# power.net
KiCad netlist of a schematic drawn in Altium Designer
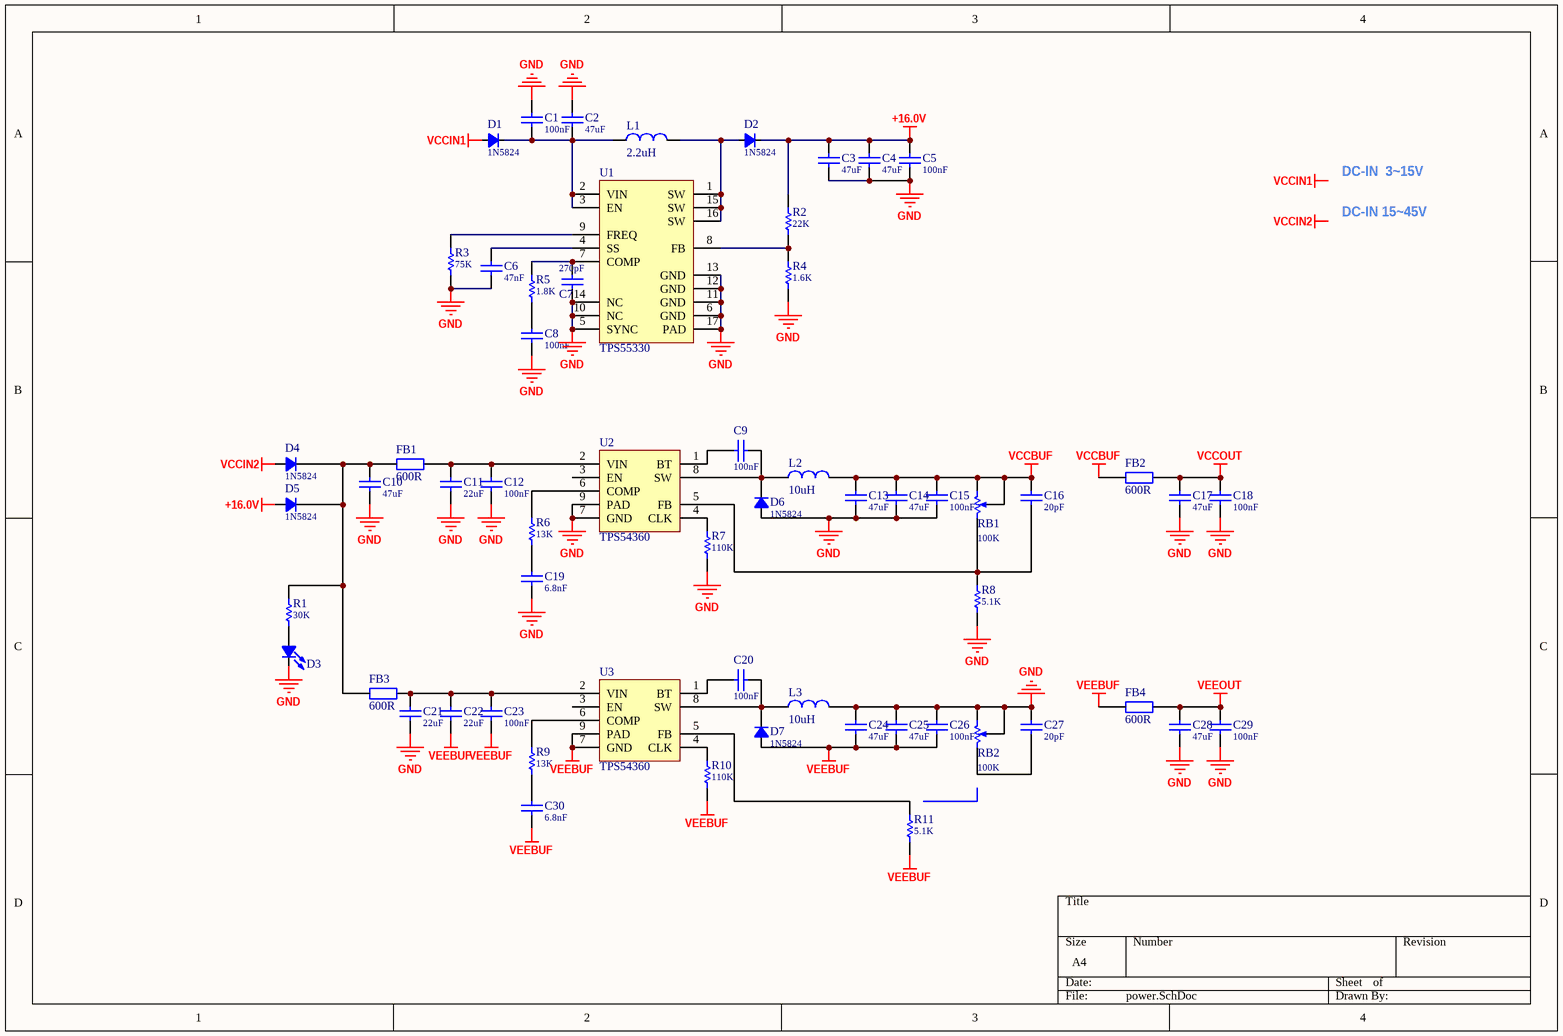
[diagram p0: power.SchDoc]

(export (version "E")
  (design (tool "Eeschema 10.0.6"))
  (components
    (comp (ref "C1")
      (value "100nF")
      (footprint "C0603-L")
      (description "贴片瓷片电容")
      (fields (field (name "Comment") "Cap-S"))
      (libsource (lib "xz_D") (part "Cap-S"))
    )
    (comp (ref "C2")
      (value "47uF")
      (footprint "C1206-L")
      (description "贴片瓷片电容")
      (fields (field (name "Comment") "Cap-S"))
      (libsource (lib "xz_D") (part "Cap-S"))
    )
    (comp (ref "C3")
      (value "47uF")
      (footprint "C1206-L")
      (description "贴片瓷片电容")
      (fields (field (name "Comment") "Cap-S"))
      (libsource (lib "xz_D") (part "Cap-S"))
    )
    (comp (ref "C4")
      (value "47uF")
      (footprint "C1206-L")
      (description "贴片瓷片电容")
      (fields (field (name "Comment") "Cap-S"))
      (libsource (lib "xz_D") (part "Cap-S"))
    )
    (comp (ref "C5")
      (value "100nF")
      (footprint "C0603-L")
      (description "贴片瓷片电容")
      (fields (field (name "Comment") "Cap-S"))
      (libsource (lib "xz_D") (part "Cap-S"))
    )
    (comp (ref "C6")
      (value "47nF")
      (footprint "C0603-L")
      (description "贴片瓷片电容")
      (fields (field (name "Comment") "Cap-S"))
      (libsource (lib "xz_D") (part "Cap-S"))
    )
    (comp (ref "C7")
      (value "270pF")
      (footprint "C0603-L")
      (description "贴片瓷片电容")
      (fields (field (name "Comment") "Cap-S"))
      (libsource (lib "xz_D") (part "Cap-S"))
    )
    (comp (ref "C8")
      (value "100nF")
      (footprint "C0603-L")
      (description "贴片瓷片电容")
      (fields (field (name "Comment") "Cap-S"))
      (libsource (lib "xz_D") (part "Cap-S"))
    )
    (comp (ref "C9")
      (value "100nF")
      (footprint "C0603-L")
      (description "贴片瓷片电容")
      (fields (field (name "Comment") "Cap-S"))
      (libsource (lib "xz_D") (part "Cap-S"))
    )
    (comp (ref "C10")
      (value "47uF")
      (footprint "C1206-L")
      (description "贴片瓷片电容")
      (fields (field (name "Comment") "Cap-S"))
      (libsource (lib "xz_D") (part "Cap-S"))
    )
    (comp (ref "C11")
      (value "22uF")
      (footprint "C1206-L")
      (description "贴片瓷片电容")
      (fields (field (name "Comment") "Cap-S"))
      (libsource (lib "xz_D") (part "Cap-S"))
    )
    (comp (ref "C12")
      (value "100nF")
      (footprint "C0603-L")
      (description "贴片瓷片电容")
      (fields (field (name "Comment") "Cap-S"))
      (libsource (lib "xz_D") (part "Cap-S"))
    )
    (comp (ref "C13")
      (value "47uF")
      (footprint "C1206-L")
      (description "贴片瓷片电容")
      (fields (field (name "Comment") "Cap-S"))
      (libsource (lib "xz_D") (part "Cap-S"))
    )
    (comp (ref "C14")
      (value "47uF")
      (footprint "C1206-L")
      (description "贴片瓷片电容")
      (fields (field (name "Comment") "Cap-S"))
      (libsource (lib "xz_D") (part "Cap-S"))
    )
    (comp (ref "C15")
      (value "100nF")
      (footprint "C0603-L")
      (description "贴片瓷片电容")
      (fields (field (name "Comment") "Cap-S"))
      (libsource (lib "xz_D") (part "Cap-S"))
    )
    (comp (ref "C16")
      (value "20pF")
      (footprint "C0603-L")
      (description "贴片瓷片电容")
      (fields (field (name "Comment") "Cap-S"))
      (libsource (lib "xz_D") (part "Cap-S"))
    )
    (comp (ref "C17")
      (value "47uF")
      (footprint "C1206-L")
      (description "贴片瓷片电容")
      (fields (field (name "Comment") "Cap-S"))
      (libsource (lib "xz_D") (part "Cap-S"))
    )
    (comp (ref "C18")
      (value "100nF")
      (footprint "C0603-L")
      (description "贴片瓷片电容")
      (fields (field (name "Comment") "Cap-S"))
      (libsource (lib "xz_D") (part "Cap-S"))
    )
    (comp (ref "C19")
      (value "6.8nF")
      (footprint "C0603-L")
      (description "贴片瓷片电容")
      (fields (field (name "Comment") "Cap-S"))
      (libsource (lib "xz_D") (part "Cap-S"))
    )
    (comp (ref "C20")
      (value "100nF")
      (footprint "C0603-L")
      (description "贴片瓷片电容")
      (fields (field (name "Comment") "Cap-S"))
      (libsource (lib "xz_D") (part "Cap-S"))
    )
    (comp (ref "C21")
      (value "22uF")
      (footprint "C1206-L")
      (description "贴片瓷片电容")
      (fields (field (name "Comment") "Cap-S"))
      (libsource (lib "xz_D") (part "Cap-S"))
    )
    (comp (ref "C22")
      (value "22uF")
      (footprint "C1206-L")
      (description "贴片瓷片电容")
      (fields (field (name "Comment") "Cap-S"))
      (libsource (lib "xz_D") (part "Cap-S"))
    )
    (comp (ref "C23")
      (value "100nF")
      (footprint "C0603-L")
      (description "贴片瓷片电容")
      (fields (field (name "Comment") "Cap-S"))
      (libsource (lib "xz_D") (part "Cap-S"))
    )
    (comp (ref "C24")
      (value "47uF")
      (footprint "C1206-L")
      (description "贴片瓷片电容")
      (fields (field (name "Comment") "Cap-S"))
      (libsource (lib "xz_D") (part "Cap-S"))
    )
    (comp (ref "C25")
      (value "47uF")
      (footprint "C1206-L")
      (description "贴片瓷片电容")
      (fields (field (name "Comment") "Cap-S"))
      (libsource (lib "xz_D") (part "Cap-S"))
    )
    (comp (ref "C26")
      (value "100nF")
      (footprint "C0603-L")
      (description "贴片瓷片电容")
      (fields (field (name "Comment") "Cap-S"))
      (libsource (lib "xz_D") (part "Cap-S"))
    )
    (comp (ref "C27")
      (value "20pF")
      (footprint "C0603-L")
      (description "贴片瓷片电容")
      (fields (field (name "Comment") "Cap-S"))
      (libsource (lib "xz_D") (part "Cap-S"))
    )
    (comp (ref "C28")
      (value "47uF")
      (footprint "C1206-L")
      (description "贴片瓷片电容")
      (fields (field (name "Comment") "Cap-S"))
      (libsource (lib "xz_D") (part "Cap-S"))
    )
    (comp (ref "C29")
      (value "100nF")
      (footprint "C0603-L")
      (description "贴片瓷片电容")
      (fields (field (name "Comment") "Cap-S"))
      (libsource (lib "xz_D") (part "Cap-S"))
    )
    (comp (ref "C30")
      (value "6.8nF")
      (footprint "C0603-L")
      (description "贴片瓷片电容")
      (fields (field (name "Comment") "Cap-S"))
      (libsource (lib "xz_D") (part "Cap-S"))
    )
    (comp (ref "D1")
      (value "D")
      (footprint "D-SMA")
      (description "二极管")
      (fields (field (name "MODEL") "1N5824"))
      (libsource (lib "xz_D") (part "Diode"))
    )
    (comp (ref "D2")
      (value "D")
      (footprint "D-SMA")
      (description "二极管")
      (fields (field (name "MODEL") "1N5824"))
      (libsource (lib "xz_D") (part "Diode"))
    )
    (comp (ref "D3")
      (value "LED")
      (footprint "Led-0805_M")
      (description "发光二极管")
      (libsource (lib "xz_D") (part "LED"))
    )
    (comp (ref "D4")
      (value "D")
      (footprint "D-SMA")
      (description "二极管")
      (fields (field (name "MODEL") "1N5824"))
      (libsource (lib "xz_D") (part "Diode"))
    )
    (comp (ref "D5")
      (value "D")
      (footprint "D-SMA")
      (description "二极管")
      (fields (field (name "MODEL") "1N5824"))
      (libsource (lib "xz_D") (part "Diode"))
    )
    (comp (ref "D6")
      (value "D")
      (footprint "D-SMA")
      (description "二极管")
      (fields (field (name "MODEL") "1N5824"))
      (libsource (lib "xz_D") (part "Diode"))
    )
    (comp (ref "D7")
      (value "D")
      (footprint "D-SMA")
      (description "二极管")
      (fields (field (name "MODEL") "1N5824"))
      (libsource (lib "xz_D") (part "Diode"))
    )
    (comp (ref "FB1") (value "600R") (footprint "FB-0805") (libsource (lib "CommonUsed") (part "FB")))
    (comp (ref "FB2") (value "600R") (footprint "FB-0805") (libsource (lib "CommonUsed") (part "FB")))
    (comp (ref "FB3") (value "600R") (footprint "FB-0805") (libsource (lib "CommonUsed") (part "FB")))
    (comp (ref "FB4") (value "600R") (footprint "FB-0805") (libsource (lib "CommonUsed") (part "FB")))
    (comp (ref "L1") (value "2.2uH") (footprint "L-6.5mm") (libsource (lib "CommonUsed") (part "Inductor")))
    (comp (ref "L2") (value "10uH") (footprint "L-6.5mm") (libsource (lib "CommonUsed") (part "Inductor")))
    (comp (ref "L3") (value "10uH") (footprint "L-6.5mm") (libsource (lib "CommonUsed") (part "Inductor")))
    (comp (ref "R1")
      (value "30K")
      (footprint "R0603-L")
      (description "贴片电阻")
      (fields (field (name "Comment") "R"))
      (libsource (lib "xz_D") (part "Res"))
    )
    (comp (ref "R2")
      (value "22K")
      (footprint "R0603-L")
      (description "贴片电阻")
      (fields (field (name "Comment") "R"))
      (libsource (lib "xz_D") (part "Res"))
    )
    (comp (ref "R3")
      (value "75K")
      (footprint "R0603-L")
      (description "贴片电阻")
      (fields (field (name "Comment") "R"))
      (libsource (lib "xz_D") (part "Res"))
    )
    (comp (ref "R4")
      (value "1.6K")
      (footprint "R0603-L")
      (description "贴片电阻")
      (fields (field (name "Comment") "R"))
      (libsource (lib "xz_D") (part "Res"))
    )
    (comp (ref "R5")
      (value "1.8K")
      (footprint "R0603-L")
      (description "贴片电阻")
      (fields (field (name "Comment") "R"))
      (libsource (lib "xz_D") (part "Res"))
    )
    (comp (ref "R6")
      (value "13K")
      (footprint "R0603-L")
      (description "贴片电阻")
      (fields (field (name "Comment") "R"))
      (libsource (lib "xz_D") (part "Res"))
    )
    (comp (ref "R7")
      (value "110K")
      (footprint "R0603-L")
      (description "贴片电阻")
      (fields (field (name "Comment") "R"))
      (libsource (lib "xz_D") (part "Res"))
    )
    (comp (ref "R8")
      (value "5.1K")
      (footprint "R0603-L")
      (description "贴片电阻")
      (fields (field (name "Comment") "R"))
      (libsource (lib "xz_D") (part "Res"))
    )
    (comp (ref "R9")
      (value "13K")
      (footprint "R0603-L")
      (description "贴片电阻")
      (fields (field (name "Comment") "R"))
      (libsource (lib "xz_D") (part "Res"))
    )
    (comp (ref "R10")
      (value "110K")
      (footprint "R0603-L")
      (description "贴片电阻")
      (fields (field (name "Comment") "R"))
      (libsource (lib "xz_D") (part "Res"))
    )
    (comp (ref "R11")
      (value "5.1K")
      (footprint "R0603-L")
      (description "贴片电阻")
      (fields (field (name "Comment") "R"))
      (libsource (lib "xz_D") (part "Res"))
    )
    (comp (ref "RB1")
      (value "100K")
      (footprint "R_VR-3296W")
      (description "可调电阻")
      (fields (field (name "Comment") "R"))
      (libsource (lib "xz_D") (part "Res_Val"))
    )
    (comp (ref "RB2")
      (value "100K")
      (footprint "R_VR-3296W")
      (description "可调电阻")
      (fields (field (name "Comment") "R"))
      (libsource (lib "xz_D") (part "Res_Val"))
    )
    (comp (ref "U1")
      (value "TPS55330")
      (footprint "VQFN-16")
      (libsource (lib "CommonUsed") (part "TPS55330"))
    )
    (comp (ref "U2")
      (value "TPS54360")
      (footprint "SOP-8 with pad")
      (libsource (lib "CommonUsed") (part "TPS54560"))
    )
    (comp (ref "U3")
      (value "TPS54360")
      (footprint "SOP-8 with pad")
      (libsource (lib "CommonUsed") (part "TPS54560"))
    )
  )
  (nets
    (net (code "1") (name "+16.0V") (class "Default")
      (node (ref "C3") (pin "2") (pinfunction "2_2") (pintype "passive"))
      (node (ref "C4") (pin "2") (pinfunction "2_2") (pintype "passive"))
      (node (ref "C5") (pin "2") (pinfunction "2_2") (pintype "passive"))
      (node (ref "D2") (pin "2") (pinfunction "K_2") (pintype "passive"))
      (node (ref "D5") (pin "1") (pinfunction "A_1") (pintype "passive"))
      (node (ref "R2") (pin "2") (pinfunction "2_2") (pintype "passive"))
    )
    (net (code "2") (name "GND") (class "Default")
      (node (ref "C1") (pin "2") (pinfunction "2_2") (pintype "passive"))
      (node (ref "C10") (pin "1") (pinfunction "1_1") (pintype "passive"))
      (node (ref "C11") (pin "1") (pinfunction "1_1") (pintype "passive"))
      (node (ref "C12") (pin "1") (pinfunction "1_1") (pintype "passive"))
      (node (ref "C13") (pin "1") (pinfunction "1_1") (pintype "passive"))
      (node (ref "C14") (pin "1") (pinfunction "1_1") (pintype "passive"))
      (node (ref "C15") (pin "1") (pinfunction "1_1") (pintype "passive"))
      (node (ref "C17") (pin "1") (pinfunction "1_1") (pintype "passive"))
      (node (ref "C18") (pin "1") (pinfunction "1_1") (pintype "passive"))
      (node (ref "C19") (pin "1") (pinfunction "1_1") (pintype "passive"))
      (node (ref "C2") (pin "2") (pinfunction "2_2") (pintype "passive"))
      (node (ref "C21") (pin "1") (pinfunction "1_1") (pintype "passive"))
      (node (ref "C24") (pin "2") (pinfunction "2_2") (pintype "passive"))
      (node (ref "C25") (pin "2") (pinfunction "2_2") (pintype "passive"))
      (node (ref "C26") (pin "2") (pinfunction "2_2") (pintype "passive"))
      (node (ref "C27") (pin "2") (pinfunction "2_2") (pintype "passive"))
      (node (ref "C28") (pin "1") (pinfunction "1_1") (pintype "passive"))
      (node (ref "C29") (pin "1") (pinfunction "1_1") (pintype "passive"))
      (node (ref "C3") (pin "1") (pinfunction "1_1") (pintype "passive"))
      (node (ref "C4") (pin "1") (pinfunction "1_1") (pintype "passive"))
      (node (ref "C5") (pin "1") (pinfunction "1_1") (pintype "passive"))
      (node (ref "C6") (pin "1") (pinfunction "1_1") (pintype "passive"))
      (node (ref "C7") (pin "1") (pinfunction "1_1") (pintype "passive"))
      (node (ref "C8") (pin "1") (pinfunction "1_1") (pintype "passive"))
      (node (ref "D3") (pin "2") (pinfunction "2_2") (pintype "passive"))
      (node (ref "D6") (pin "1") (pinfunction "A_1") (pintype "passive"))
      (node (ref "L3") (pin "2") (pinfunction "2_2") (pintype "passive"))
      (node (ref "R3") (pin "2") (pinfunction "2_2") (pintype "passive"))
      (node (ref "R4") (pin "1") (pinfunction "1_1") (pintype "passive"))
      (node (ref "R7") (pin "1") (pinfunction "1_1") (pintype "passive"))
      (node (ref "R8") (pin "1") (pinfunction "1_1") (pintype "passive"))
      (node (ref "RB2") (pin "2") (pinfunction "2_2") (pintype "passive"))
      (node (ref "RB2") (pin "3") (pinfunction "3_3") (pintype "passive"))
      (node (ref "U1") (pin "10") (pinfunction "NC_10") (pintype "passive"))
      (node (ref "U1") (pin "11") (pinfunction "GND_11") (pintype "passive"))
      (node (ref "U1") (pin "12") (pinfunction "GND_12") (pintype "passive"))
      (node (ref "U1") (pin "13") (pinfunction "GND_13") (pintype "passive"))
      (node (ref "U1") (pin "14") (pinfunction "NC_14") (pintype "passive"))
      (node (ref "U1") (pin "17") (pinfunction "PAD_17") (pintype "passive"))
      (node (ref "U1") (pin "5") (pinfunction "SYNC_5") (pintype "passive"))
      (node (ref "U1") (pin "6") (pinfunction "GND_6") (pintype "passive"))
      (node (ref "U2") (pin "7") (pinfunction "GND_7") (pintype "passive"))
      (node (ref "U2") (pin "9") (pinfunction "PAD_9") (pintype "passive"))
    )
    (net (code "3") (name "Net-(C8-Pad2)") (class "Default")
      (node (ref "C8") (pin "2") (pinfunction "2_2") (pintype "passive"))
      (node (ref "R5") (pin "2") (pinfunction "2_2") (pintype "passive"))
    )
    (net (code "4") (name "Net-(C19-Pad2)") (class "Default")
      (node (ref "C19") (pin "2") (pinfunction "2_2") (pintype "passive"))
      (node (ref "R6") (pin "1") (pinfunction "1_1") (pintype "passive"))
    )
    (net (code "5") (name "Net-(C27-Pad1)") (class "Default")
      (node (ref "C27") (pin "1") (pinfunction "1_1") (pintype "passive"))
      (node (ref "RB2") (pin "1") (pinfunction "1_1") (pintype "passive"))
    )
    (net (code "6") (name "Net-(C30-Pad2)") (class "Default")
      (node (ref "C30") (pin "2") (pinfunction "2_2") (pintype "passive"))
      (node (ref "R9") (pin "1") (pinfunction "1_1") (pintype "passive"))
    )
    (net (code "7") (name "Net-(D1-K)") (class "Default")
      (node (ref "C1") (pin "1") (pinfunction "1_1") (pintype "passive"))
      (node (ref "C2") (pin "1") (pinfunction "1_1") (pintype "passive"))
      (node (ref "D1") (pin "2") (pinfunction "K_2") (pintype "passive"))
      (node (ref "L1") (pin "1") (pinfunction "1_1") (pintype "passive"))
      (node (ref "U1") (pin "2") (pinfunction "VIN_2") (pintype "passive"))
      (node (ref "U1") (pin "3") (pinfunction "EN_3") (pintype "passive"))
    )
    (net (code "8") (name "Net-(D2-A)") (class "Default")
      (node (ref "D2") (pin "1") (pinfunction "A_1") (pintype "passive"))
      (node (ref "L1") (pin "2") (pinfunction "2_2") (pintype "passive"))
      (node (ref "U1") (pin "1") (pinfunction "SW_1") (pintype "passive"))
      (node (ref "U1") (pin "15") (pinfunction "SW_15") (pintype "passive"))
      (node (ref "U1") (pin "16") (pinfunction "SW_16") (pintype "passive"))
    )
    (net (code "9") (name "Net-(D3-Pad1)") (class "Default")
      (node (ref "D3") (pin "1") (pinfunction "1_1") (pintype "passive"))
      (node (ref "R1") (pin "1") (pinfunction "1_1") (pintype "passive"))
    )
    (net (code "10") (name "Net-(D4-K)") (class "Default")
      (node (ref "C10") (pin "2") (pinfunction "2_2") (pintype "passive"))
      (node (ref "D4") (pin "2") (pinfunction "K_2") (pintype "passive"))
      (node (ref "D5") (pin "2") (pinfunction "K_2") (pintype "passive"))
      (node (ref "FB1") (pin "1") (pinfunction "1_1") (pintype "passive"))
      (node (ref "FB3") (pin "1") (pinfunction "1_1") (pintype "passive"))
      (node (ref "R1") (pin "2") (pinfunction "2_2") (pintype "passive"))
    )
    (net (code "11") (name "Net-(D6-K)") (class "Default")
      (node (ref "C9") (pin "2") (pinfunction "2_2") (pintype "passive"))
      (node (ref "D6") (pin "2") (pinfunction "K_2") (pintype "passive"))
      (node (ref "L2") (pin "1") (pinfunction "1_1") (pintype "passive"))
      (node (ref "U2") (pin "8") (pinfunction "SW_8") (pintype "passive"))
    )
    (net (code "12") (name "Net-(D7-K)") (class "Default")
      (node (ref "C20") (pin "2") (pinfunction "2_2") (pintype "passive"))
      (node (ref "D7") (pin "2") (pinfunction "K_2") (pintype "passive"))
      (node (ref "L3") (pin "1") (pinfunction "1_1") (pintype "passive"))
      (node (ref "U3") (pin "8") (pinfunction "SW_8") (pintype "passive"))
    )
    (net (code "13") (name "Net-(U1-COMP)") (class "Default")
      (node (ref "C7") (pin "2") (pinfunction "2_2") (pintype "passive"))
      (node (ref "R5") (pin "1") (pinfunction "1_1") (pintype "passive"))
      (node (ref "U1") (pin "7") (pinfunction "COMP_7") (pintype "passive"))
    )
    (net (code "14") (name "Net-(U1-FB)") (class "Default")
      (node (ref "R2") (pin "1") (pinfunction "1_1") (pintype "passive"))
      (node (ref "R4") (pin "2") (pinfunction "2_2") (pintype "passive"))
      (node (ref "U1") (pin "8") (pinfunction "FB_8") (pintype "passive"))
    )
    (net (code "15") (name "Net-(U1-FREQ)") (class "Default")
      (node (ref "R3") (pin "1") (pinfunction "1_1") (pintype "passive"))
      (node (ref "U1") (pin "9") (pinfunction "FREQ_9") (pintype "passive"))
    )
    (net (code "16") (name "Net-(U1-SS)") (class "Default")
      (node (ref "C6") (pin "2") (pinfunction "2_2") (pintype "passive"))
      (node (ref "U1") (pin "4") (pinfunction "SS_4") (pintype "passive"))
    )
    (net (code "17") (name "Net-(U2-BT)") (class "Default")
      (node (ref "C9") (pin "1") (pinfunction "1_1") (pintype "passive"))
      (node (ref "U2") (pin "1") (pinfunction "BT_1") (pintype "passive"))
    )
    (net (code "18") (name "Net-(U2-CLK)") (class "Default")
      (node (ref "R7") (pin "2") (pinfunction "2_2") (pintype "passive"))
      (node (ref "U2") (pin "4") (pinfunction "CLK_4") (pintype "passive"))
    )
    (net (code "19") (name "Net-(U2-COMP)") (class "Default")
      (node (ref "R6") (pin "2") (pinfunction "2_2") (pintype "passive"))
      (node (ref "U2") (pin "6") (pinfunction "COMP_6") (pintype "passive"))
    )
    (net (code "20") (name "Net-(U2-FB)") (class "Default")
      (node (ref "C16") (pin "1") (pinfunction "1_1") (pintype "passive"))
      (node (ref "R8") (pin "2") (pinfunction "2_2") (pintype "passive"))
      (node (ref "RB1") (pin "1") (pinfunction "1_1") (pintype "passive"))
      (node (ref "U2") (pin "5") (pinfunction "FB_5") (pintype "passive"))
    )
    (net (code "21") (name "Net-(U2-VIN)") (class "Default")
      (node (ref "C11") (pin "2") (pinfunction "2_2") (pintype "passive"))
      (node (ref "C12") (pin "2") (pinfunction "2_2") (pintype "passive"))
      (node (ref "FB1") (pin "2") (pinfunction "2_2") (pintype "passive"))
      (node (ref "U2") (pin "2") (pinfunction "VIN_2") (pintype "passive"))
    )
    (net (code "22") (name "Net-(U3-BT)") (class "Default")
      (node (ref "C20") (pin "1") (pinfunction "1_1") (pintype "passive"))
      (node (ref "U3") (pin "1") (pinfunction "BT_1") (pintype "passive"))
    )
    (net (code "23") (name "Net-(U3-CLK)") (class "Default")
      (node (ref "R10") (pin "2") (pinfunction "2_2") (pintype "passive"))
      (node (ref "U3") (pin "4") (pinfunction "CLK_4") (pintype "passive"))
    )
    (net (code "24") (name "Net-(U3-COMP)") (class "Default")
      (node (ref "R9") (pin "2") (pinfunction "2_2") (pintype "passive"))
      (node (ref "U3") (pin "6") (pinfunction "COMP_6") (pintype "passive"))
    )
    (net (code "25") (name "Net-(U3-FB)") (class "Default")
      (node (ref "R11") (pin "2") (pinfunction "2_2") (pintype "passive"))
      (node (ref "U3") (pin "5") (pinfunction "FB_5") (pintype "passive"))
    )
    (net (code "26") (name "Net-(U3-VIN)") (class "Default")
      (node (ref "C21") (pin "2") (pinfunction "2_2") (pintype "passive"))
      (node (ref "C22") (pin "2") (pinfunction "2_2") (pintype "passive"))
      (node (ref "C23") (pin "2") (pinfunction "2_2") (pintype "passive"))
      (node (ref "FB3") (pin "2") (pinfunction "2_2") (pintype "passive"))
      (node (ref "U3") (pin "2") (pinfunction "VIN_2") (pintype "passive"))
    )
    (net (code "27") (name "VCCBUF") (class "Default")
      (node (ref "C13") (pin "2") (pinfunction "2_2") (pintype "passive"))
      (node (ref "C14") (pin "2") (pinfunction "2_2") (pintype "passive"))
      (node (ref "C15") (pin "2") (pinfunction "2_2") (pintype "passive"))
      (node (ref "C16") (pin "2") (pinfunction "2_2") (pintype "passive"))
      (node (ref "FB2") (pin "1") (pinfunction "1_1") (pintype "passive"))
      (node (ref "L2") (pin "2") (pinfunction "2_2") (pintype "passive"))
      (node (ref "RB1") (pin "2") (pinfunction "2_2") (pintype "passive"))
      (node (ref "RB1") (pin "3") (pinfunction "3_3") (pintype "passive"))
    )
    (net (code "28") (name "VCCIN1") (class "Default")
      (node (ref "D1") (pin "1") (pinfunction "A_1") (pintype "passive"))
    )
    (net (code "29") (name "VCCIN2") (class "Default")
      (node (ref "D4") (pin "1") (pinfunction "A_1") (pintype "passive"))
    )
    (net (code "30") (name "VCCOUT") (class "Default")
      (node (ref "C17") (pin "2") (pinfunction "2_2") (pintype "passive"))
      (node (ref "C18") (pin "2") (pinfunction "2_2") (pintype "passive"))
      (node (ref "FB2") (pin "2") (pinfunction "2_2") (pintype "passive"))
    )
    (net (code "31") (name "VEEBUF") (class "Default")
      (node (ref "C22") (pin "1") (pinfunction "1_1") (pintype "passive"))
      (node (ref "C23") (pin "1") (pinfunction "1_1") (pintype "passive"))
      (node (ref "C24") (pin "1") (pinfunction "1_1") (pintype "passive"))
      (node (ref "C25") (pin "1") (pinfunction "1_1") (pintype "passive"))
      (node (ref "C26") (pin "1") (pinfunction "1_1") (pintype "passive"))
      (node (ref "C30") (pin "1") (pinfunction "1_1") (pintype "passive"))
      (node (ref "D7") (pin "1") (pinfunction "A_1") (pintype "passive"))
      (node (ref "FB4") (pin "1") (pinfunction "1_1") (pintype "passive"))
      (node (ref "R10") (pin "1") (pinfunction "1_1") (pintype "passive"))
      (node (ref "R11") (pin "1") (pinfunction "1_1") (pintype "passive"))
      (node (ref "U3") (pin "7") (pinfunction "GND_7") (pintype "passive"))
      (node (ref "U3") (pin "9") (pinfunction "PAD_9") (pintype "passive"))
    )
    (net (code "32") (name "VEEOUT") (class "Default")
      (node (ref "C28") (pin "2") (pinfunction "2_2") (pintype "passive"))
      (node (ref "C29") (pin "2") (pinfunction "2_2") (pintype "passive"))
      (node (ref "FB4") (pin "2") (pinfunction "2_2") (pintype "passive"))
    )
    (net (code "33") (name "unconnected-(U2-EN-Pad3)") (class "Default")
      (node (ref "U2") (pin "3") (pinfunction "EN_3") (pintype "passive"))
    )
    (net (code "34") (name "unconnected-(U3-EN-Pad3)") (class "Default")
      (node (ref "U3") (pin "3") (pinfunction "EN_3") (pintype "passive"))
    )
  )
)
